# power.net
KiCad netlist of a schematic drawn in Altium Designer
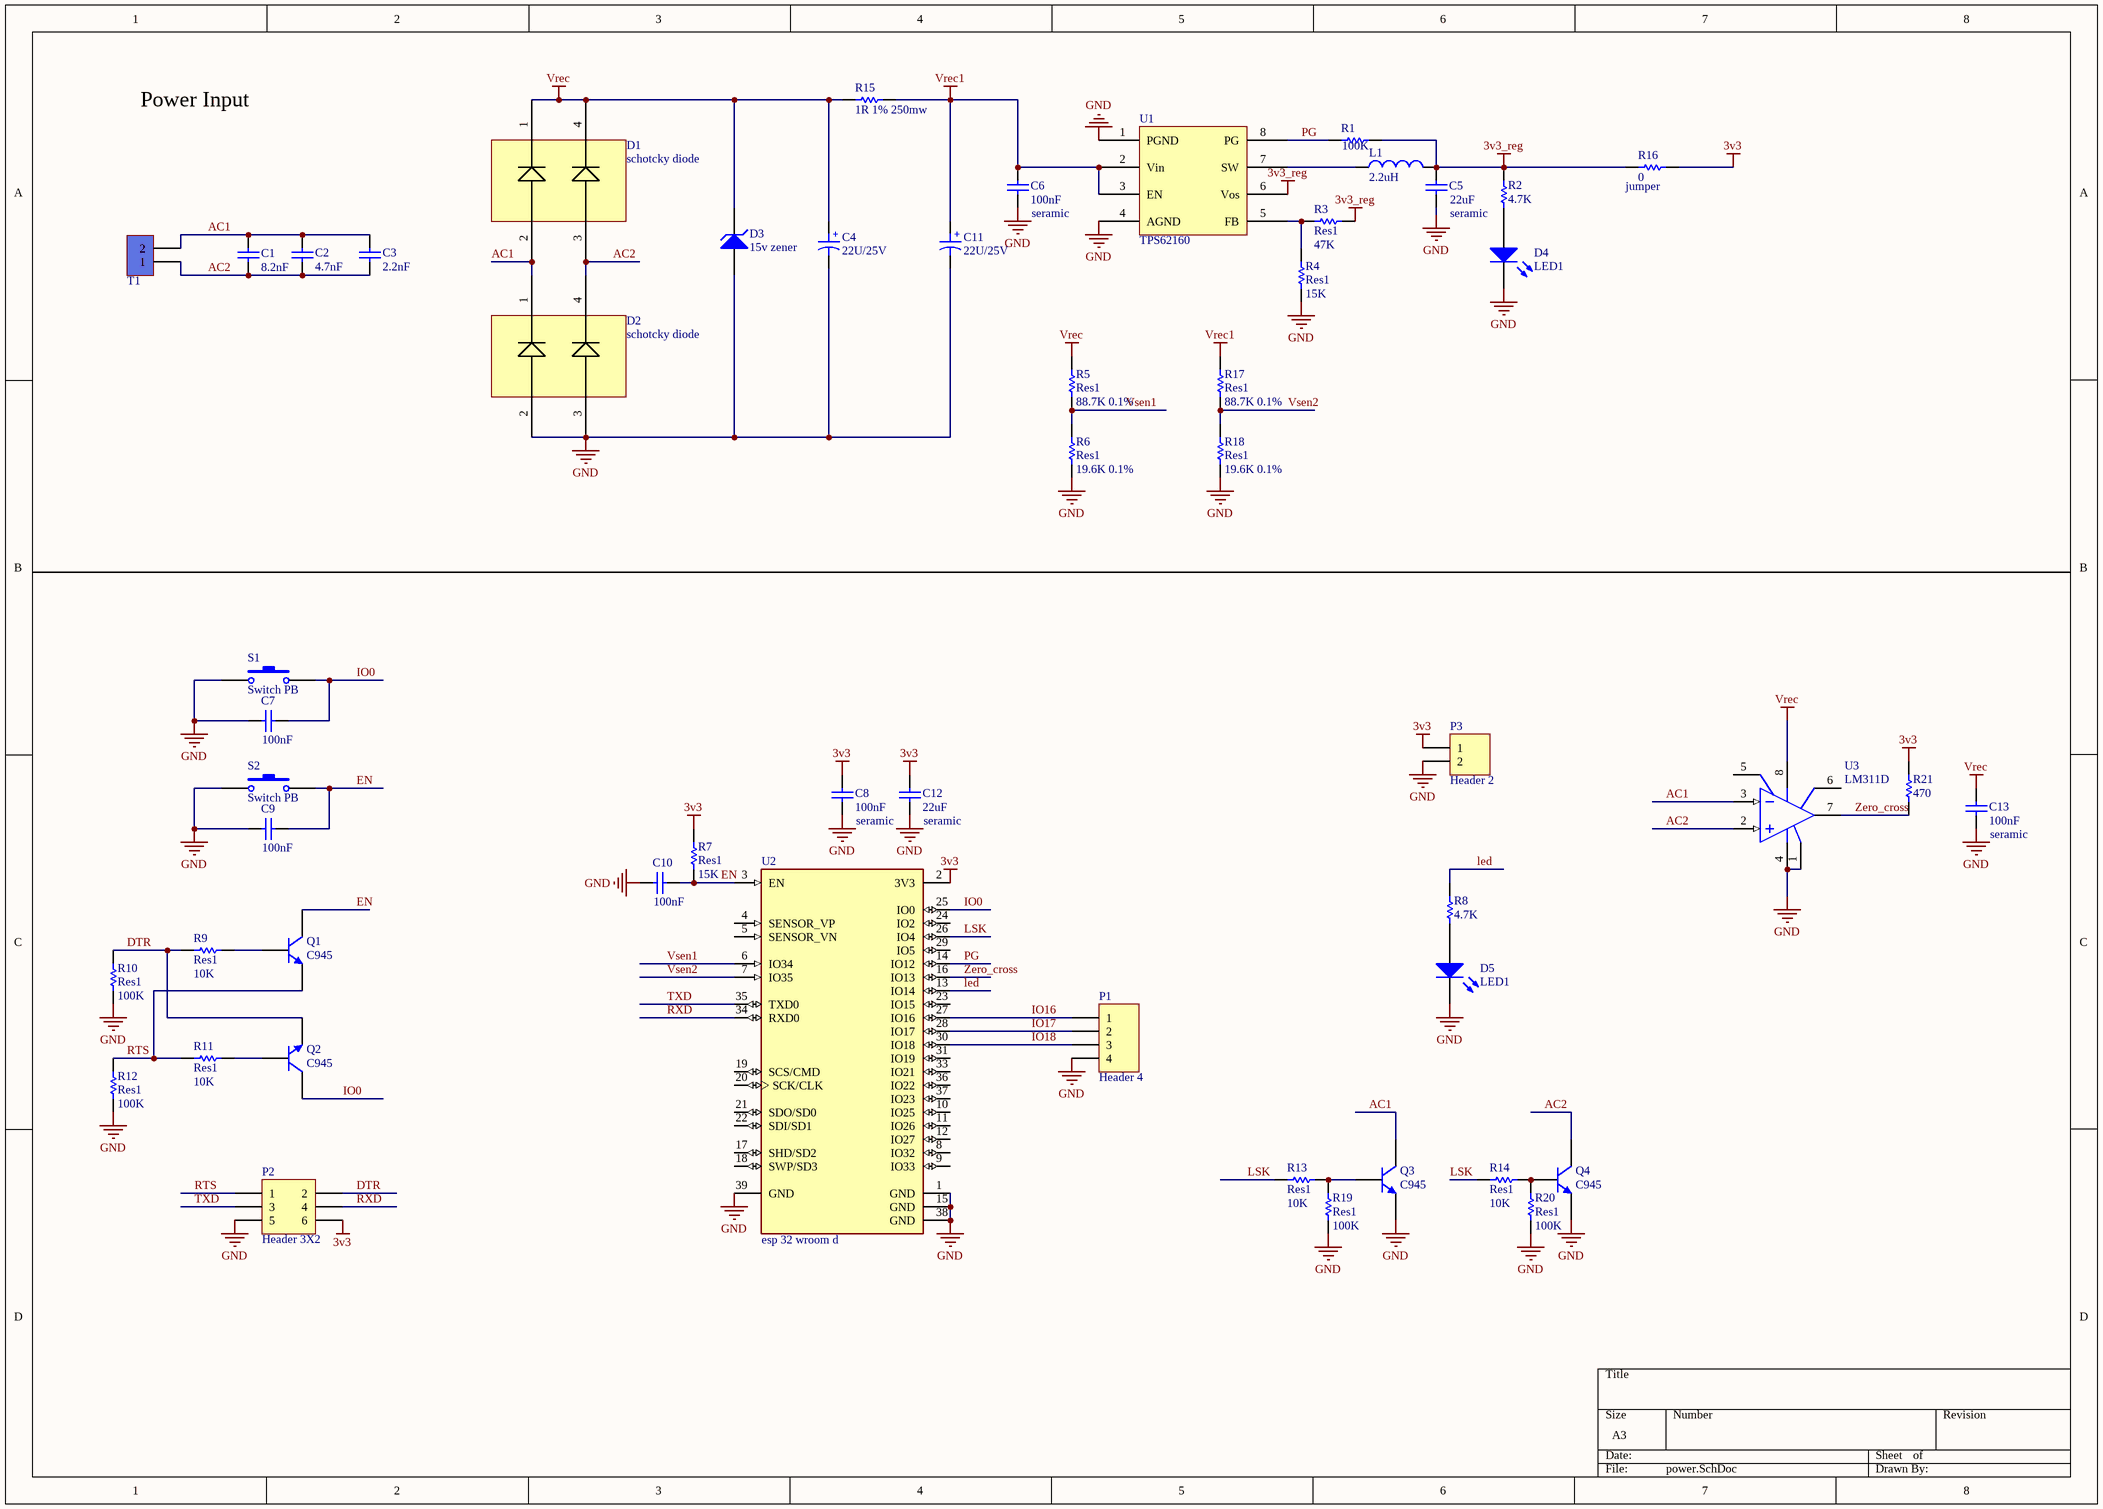
[diagram p0: power.SchDoc]

(export (version "E")
  (design (tool "Eeschema 10.0.6"))
  (components
    (comp (ref "C1")
      (value "8.2nF")
      (footprint "Cap 1206 (3216X15L)")
      (description "Capacitor")
      (fields (field (name "Comment") "Cap") (field (name "PUBLISHER") "Altium Limited"))
      (libsource (lib "Miscellaneous Devices") (part "Cap"))
    )
    (comp (ref "C2")
      (value "4.7nF")
      (footprint "Cap 1206 (3216X15L)")
      (description "Capacitor")
      (fields (field (name "Comment") "Cap") (field (name "PUBLISHER") "Altium Limited"))
      (libsource (lib "Miscellaneous Devices") (part "Cap"))
    )
    (comp (ref "C3")
      (value "2.2nF")
      (footprint "Cap 1206 (3216X15L)")
      (description "Capacitor")
      (fields (field (name "Comment") "Cap") (field (name "PUBLISHER") "Altium Limited"))
      (libsource (lib "Miscellaneous Devices") (part "Cap"))
    )
    (comp (ref "C4")
      (value "Cap tantal")
      (footprint "Cap1206_(3216X18L)Size A")
      (fields (field (name "PART. NO") "22U/25V") (field (name "DESIGNER") "Abbas Basereh"))
      (libsource (lib "Altium (2)") (part "Cap electrolitic radial 10x21"))
    )
    (comp (ref "C5")
      (value "seramic")
      (footprint "SMD_CAP_0805")
      (description "Capacitor")
      (fields (field (name "ALTIUM_VALUE") "22uF") (field (name "PUBLISHER") "Altium Limited"))
      (libsource (lib "Miscellaneous Devices") (part "Cap"))
    )
    (comp (ref "C6")
      (value "seramic")
      (footprint "SMD_CAP_0805")
      (description "Capacitor")
      (fields (field (name "ALTIUM_VALUE") "100nF") (field (name "PUBLISHER") "Altium Limited"))
      (libsource (lib "Miscellaneous Devices") (part "Cap"))
    )
    (comp (ref "C7")
      (value "100nF")
      (footprint "SMD_CAP_0805")
      (description "Capacitor")
      (fields (field (name "Comment") "seramic") (field (name "PUBLISHER") "Altium Limited"))
      (libsource (lib "Miscellaneous Devices") (part "Cap"))
    )
    (comp (ref "C8")
      (value "seramic")
      (footprint "SMD_CAP_0805")
      (description "Capacitor")
      (fields (field (name "ALTIUM_VALUE") "100nF") (field (name "PUBLISHER") "Altium Limited"))
      (libsource (lib "Miscellaneous Devices") (part "Cap"))
    )
    (comp (ref "C9")
      (value "100nF")
      (footprint "SMD_CAP_0805")
      (description "Capacitor")
      (fields (field (name "Comment") "seramic") (field (name "PUBLISHER") "Altium Limited"))
      (libsource (lib "Miscellaneous Devices") (part "Cap"))
    )
    (comp (ref "C10")
      (value "100nF")
      (footprint "SMD_CAP_0805")
      (description "Capacitor")
      (fields (field (name "Comment") "seramic") (field (name "PUBLISHER") "Altium Limited"))
      (libsource (lib "Miscellaneous Devices") (part "Cap"))
    )
    (comp (ref "C11")
      (value "Cap tantal")
      (footprint "Cap1206_(3216X18L)Size A")
      (fields (field (name "PART. NO") "22U/25V") (field (name "DESIGNER") "Abbas Basereh"))
      (libsource (lib "Altium (2)") (part "Cap electrolitic radial 10x21"))
    )
    (comp (ref "C12")
      (value "seramic")
      (footprint "SMD_CAP_0805")
      (description "Capacitor")
      (fields (field (name "ALTIUM_VALUE") "22uF") (field (name "PUBLISHER") "Altium Limited"))
      (libsource (lib "Miscellaneous Devices") (part "Cap"))
    )
    (comp (ref "C13")
      (value "seramic")
      (footprint "SMD_CAP_0805")
      (description "Capacitor")
      (fields (field (name "ALTIUM_VALUE") "100nF") (field (name "PUBLISHER") "Altium Limited"))
      (libsource (lib "Miscellaneous Devices") (part "Cap"))
    )
    (comp (ref "D1")
      (value "schotcky diode")
      (footprint "UMD4")
      (libsource (lib "reciver_sch") (part "RB481"))
    )
    (comp (ref "D2")
      (value "schotcky diode")
      (footprint "UMD4")
      (libsource (lib "reciver_sch") (part "RB481"))
    )
    (comp (ref "D3")
      (value "15v zener")
      (footprint "Diode 1n4148 SMD")
      (description "Zener Diode")
      (fields (field (name "PUBLISHER") "Altium Limited"))
      (libsource (lib "Miscellaneous Devices") (part "D Zener"))
    )
    (comp (ref "D4")
      (value "LED1")
      (footprint "led_0805")
      (description "Typical RED GaAs LED")
      (fields (field (name "PUBLISHER") "Altium Limited"))
      (libsource (lib "Miscellaneous Devices") (part "LED1"))
    )
    (comp (ref "D5")
      (value "LED1")
      (footprint "led_0805")
      (description "Typical RED GaAs LED")
      (fields (field (name "PUBLISHER") "Altium Limited"))
      (libsource (lib "Miscellaneous Devices") (part "LED1"))
    )
    (comp (ref "L1")
      (value "2.2uH")
      (footprint "IND1210")
      (description "Inductor")
      (fields (field (name "PUBLISHER") "Altium Limited"))
      (libsource (lib "Altium (2)") (part "Inductor"))
    )
    (comp (ref "P1")
      (value "Header 4")
      (footprint "header-1.27mm-1*4")
      (description "Header, 4-Pin")
      (fields (field (name "PUBLISHER") "Altium Limited"))
      (libsource (lib "Miscellaneous Connectors") (part "Header 4"))
    )
    (comp (ref "P2")
      (value "Header 3X2")
      (footprint "header-1.27mm-smd-2*3")
      (description "Header, 3-Pin, Dual row")
      (fields (field (name "PUBLISHER") "Altium Limited"))
      (libsource (lib "Miscellaneous Connectors") (part "Header 3X2"))
    )
    (comp (ref "P3")
      (value "Header 2")
      (footprint "HDR1X2")
      (description "Header, 2-Pin")
      (fields (field (name "PUBLISHER") "Altium Limited"))
      (libsource (lib "Miscellaneous Connectors") (part "Header 2"))
    )
    (comp (ref "Q1")
      (value "C945")
      (footprint "SOT23_N")
      (description "NPN Silicon Epitaxial Planar Transistor")
      (fields (field (name "PUBLISHER") "Abbas Basereh"))
      (libsource (lib "Altium (2)") (part "C945"))
    )
    (comp (ref "Q2")
      (value "C945")
      (footprint "SOT23_N")
      (description "NPN Silicon Epitaxial Planar Transistor")
      (fields (field (name "PUBLISHER") "Abbas Basereh"))
      (libsource (lib "Altium (2)") (part "C945"))
    )
    (comp (ref "Q3")
      (value "C945")
      (footprint "SOT23_N")
      (description "NPN Silicon Epitaxial Planar Transistor")
      (fields (field (name "PUBLISHER") "Abbas Basereh"))
      (libsource (lib "Altium (2)") (part "C945"))
    )
    (comp (ref "Q4")
      (value "C945")
      (footprint "SOT23_N")
      (description "NPN Silicon Epitaxial Planar Transistor")
      (fields (field (name "PUBLISHER") "Abbas Basereh"))
      (libsource (lib "Altium (2)") (part "C945"))
    )
    (comp (ref "R1")
      (value "100K")
      (footprint "RES 0805 (2012X06L)")
      (description "Resistor")
      (fields (field (name "Comment") "Res1") (field (name "PUBLISHER") "Altium Limited"))
      (libsource (lib "Miscellaneous Devices") (part "Res1"))
    )
    (comp (ref "R2")
      (value "4.7K")
      (footprint "RES 0805 (2012X06L)")
      (description "Resistor")
      (fields (field (name "Comment") "Res1") (field (name "PUBLISHER") "Altium Limited"))
      (libsource (lib "Miscellaneous Devices") (part "Res1"))
    )
    (comp (ref "R3")
      (value "Res1")
      (footprint "RES 0805 (2012X06L)")
      (description "Resistor")
      (fields (field (name "ALTIUM_VALUE") "47K") (field (name "PUBLISHER") "Altium Limited"))
      (libsource (lib "Miscellaneous Devices") (part "Res1"))
    )
    (comp (ref "R4")
      (value "Res1")
      (footprint "RES 0805 (2012X06L)")
      (description "Resistor")
      (fields (field (name "ALTIUM_VALUE") "15K") (field (name "PUBLISHER") "Altium Limited"))
      (libsource (lib "Miscellaneous Devices") (part "Res1"))
    )
    (comp (ref "R5")
      (value "Res1")
      (footprint "RES 0805 (2012X06L)")
      (description "Resistor")
      (fields (field (name "ALTIUM_VALUE") "88.7K 0.1%") (field (name "PUBLISHER") "Altium Limited"))
      (libsource (lib "Miscellaneous Devices") (part "Res1"))
    )
    (comp (ref "R6")
      (value "Res1")
      (footprint "RES 0805 (2012X06L)")
      (description "Resistor")
      (fields (field (name "ALTIUM_VALUE") "19.6K 0.1%") (field (name "PUBLISHER") "Altium Limited"))
      (libsource (lib "Miscellaneous Devices") (part "Res1"))
    )
    (comp (ref "R7")
      (value "Res1")
      (footprint "RES 0805 (2012X06L)")
      (description "Resistor")
      (fields (field (name "ALTIUM_VALUE") "15K") (field (name "PUBLISHER") "Altium Limited"))
      (libsource (lib "Miscellaneous Devices") (part "Res1"))
    )
    (comp (ref "R8")
      (value "4.7K")
      (footprint "RES 0805 (2012X06L)")
      (description "Resistor")
      (fields (field (name "Comment") "Res1") (field (name "PUBLISHER") "Altium Limited"))
      (libsource (lib "Miscellaneous Devices") (part "Res1"))
    )
    (comp (ref "R9")
      (value "Res1")
      (footprint "RES 0805 (2012X06L)")
      (description "Resistor")
      (fields (field (name "ALTIUM_VALUE") "10K") (field (name "PUBLISHER") "Altium Limited"))
      (libsource (lib "Miscellaneous Devices") (part "Res1"))
    )
    (comp (ref "R10")
      (value "Res1")
      (footprint "RES 0805 (2012X06L)")
      (description "Resistor")
      (fields (field (name "ALTIUM_VALUE") "100K") (field (name "PUBLISHER") "Altium Limited"))
      (libsource (lib "Miscellaneous Devices") (part "Res1"))
    )
    (comp (ref "R11")
      (value "Res1")
      (footprint "RES 0805 (2012X06L)")
      (description "Resistor")
      (fields (field (name "ALTIUM_VALUE") "10K") (field (name "PUBLISHER") "Altium Limited"))
      (libsource (lib "Miscellaneous Devices") (part "Res1"))
    )
    (comp (ref "R12")
      (value "Res1")
      (footprint "RES 0805 (2012X06L)")
      (description "Resistor")
      (fields (field (name "ALTIUM_VALUE") "100K") (field (name "PUBLISHER") "Altium Limited"))
      (libsource (lib "Miscellaneous Devices") (part "Res1"))
    )
    (comp (ref "R13")
      (value "Res1")
      (footprint "RES 0805 (2012X06L)")
      (description "Resistor")
      (fields (field (name "ALTIUM_VALUE") "10K") (field (name "PUBLISHER") "Altium Limited"))
      (libsource (lib "Miscellaneous Devices") (part "Res1"))
    )
    (comp (ref "R14")
      (value "Res1")
      (footprint "RES 0805 (2012X06L)")
      (description "Resistor")
      (fields (field (name "ALTIUM_VALUE") "10K") (field (name "PUBLISHER") "Altium Limited"))
      (libsource (lib "Miscellaneous Devices") (part "Res1"))
    )
    (comp (ref "R15")
      (value "1R 1% 250mw")
      (footprint "RES 1206 (3216X08L)")
      (description "Resistor")
      (fields (field (name "Comment") "Res1") (field (name "PUBLISHER") "Altium Limited"))
      (libsource (lib "Miscellaneous Devices") (part "Res1"))
    )
    (comp (ref "R16")
      (value "jumper")
      (footprint "Jumper")
      (description "Resistor")
      (fields (field (name "ALTIUM_VALUE") "0") (field (name "PUBLISHER") "Altium Limited"))
      (libsource (lib "Miscellaneous Devices") (part "Res1"))
    )
    (comp (ref "R17")
      (value "Res1")
      (footprint "RES 0805 (2012X06L)")
      (description "Resistor")
      (fields (field (name "ALTIUM_VALUE") "88.7K 0.1%") (field (name "PUBLISHER") "Altium Limited"))
      (libsource (lib "Miscellaneous Devices") (part "Res1"))
    )
    (comp (ref "R18")
      (value "Res1")
      (footprint "RES 0805 (2012X06L)")
      (description "Resistor")
      (fields (field (name "ALTIUM_VALUE") "19.6K 0.1%") (field (name "PUBLISHER") "Altium Limited"))
      (libsource (lib "Miscellaneous Devices") (part "Res1"))
    )
    (comp (ref "R19")
      (value "Res1")
      (footprint "RES 0805 (2012X06L)")
      (description "Resistor")
      (fields (field (name "ALTIUM_VALUE") "100K") (field (name "PUBLISHER") "Altium Limited"))
      (libsource (lib "Miscellaneous Devices") (part "Res1"))
    )
    (comp (ref "R20")
      (value "Res1")
      (footprint "RES 0805 (2012X06L)")
      (description "Resistor")
      (fields (field (name "ALTIUM_VALUE") "100K") (field (name "PUBLISHER") "Altium Limited"))
      (libsource (lib "Miscellaneous Devices") (part "Res1"))
    )
    (comp (ref "R21")
      (value "470")
      (footprint "RES 0805 (2012X06L)")
      (description "Resistor")
      (fields (field (name "Comment") "Res1") (field (name "PUBLISHER") "Altium Limited"))
      (libsource (lib "Miscellaneous Devices") (part "Res1"))
    )
    (comp (ref "S1")
      (value "Switch PB")
      (footprint "tack-sw-3x5x6")
      (description "Push Button Switch")
      (libsource (lib "My Library") (part "Switch PB"))
    )
    (comp (ref "S2")
      (value "Switch PB")
      (footprint "tack-sw-3x5x6")
      (description "Push Button Switch")
      (libsource (lib "My Library") (part "Switch PB"))
    )
    (comp (ref "T1")
      (value "Terminal")
      (footprint "my-term")
      (description "Terminal 2 Pin 250VAC 16A")
      (fields (field (name "DESIGNER") "Seyed Mohsen Ghasemain") (field (name "E-MAIL") "picpars@gmail.com"))
      (libsource (lib "PicPars.com_usefully_Library") (part "Terminal 1*2"))
    )
    (comp (ref "U1")
      (value "TPS62160")
      (footprint "DGK-PDSO-G8")
      (libsource (lib "reciver_sch") (part "TPS62160"))
    )
    (comp (ref "U2")
      (value "esp 32 wroom d")
      (footprint "esp-wroom")
      (libsource (lib "reciver_sch") (part "ESP32-wroom"))
    )
    (comp (ref "U3")
      (value "LM311D")
      (footprint "SO8_N")
      (description "Voltage Comparator")
      (fields (field (name "PUBLISHER") "Altium Limited"))
      (libsource (lib "ST Analog Comparator") (part "LM311D"))
    )
  )
  (nets
    (net (code "1") (name "/AC1") (class "Default")
      (node (ref "C1") (pin "2") (pinfunction "2_2") (pintype "passive"))
      (node (ref "C2") (pin "2") (pinfunction "2_2") (pintype "passive"))
      (node (ref "C3") (pin "2") (pinfunction "2_2") (pintype "passive"))
      (node (ref "D1") (pin "2") (pinfunction "A1_2") (pintype "passive"))
      (node (ref "D2") (pin "1") (pinfunction "K1_1") (pintype "passive"))
      (node (ref "Q3") (pin "3") (pinfunction "C_3") (pintype "passive"))
      (node (ref "T1") (pin "2") (pinfunction "2_2") (pintype "passive"))
      (node (ref "U3") (pin "3") (pinfunction "IN-_3") (pintype "input"))
    )
    (net (code "2") (name "/AC2") (class "Default")
      (node (ref "C1") (pin "1") (pinfunction "1_1") (pintype "passive"))
      (node (ref "C2") (pin "1") (pinfunction "1_1") (pintype "passive"))
      (node (ref "C3") (pin "1") (pinfunction "1_1") (pintype "passive"))
      (node (ref "D1") (pin "3") (pinfunction "A2_3") (pintype "passive"))
      (node (ref "D2") (pin "4") (pinfunction "K2_4") (pintype "passive"))
      (node (ref "Q4") (pin "3") (pinfunction "C_3") (pintype "passive"))
      (node (ref "T1") (pin "1") (pinfunction "1_1") (pintype "passive"))
      (node (ref "U3") (pin "2") (pinfunction "IN+_2") (pintype "input"))
    )
    (net (code "3") (name "/DTR") (class "Default")
      (node (ref "P2") (pin "2") (pinfunction "2_2") (pintype "passive"))
      (node (ref "Q2") (pin "2") (pinfunction "E_2") (pintype "passive"))
      (node (ref "R10") (pin "1") (pinfunction "1_1") (pintype "passive"))
      (node (ref "R9") (pin "1") (pinfunction "1_1") (pintype "passive"))
    )
    (net (code "4") (name "/EN") (class "Default")
      (node (ref "C10") (pin "1") (pinfunction "1_1") (pintype "passive"))
      (node (ref "C9") (pin "1") (pinfunction "1_1") (pintype "passive"))
      (node (ref "Q1") (pin "3") (pinfunction "C_3") (pintype "passive"))
      (node (ref "R7") (pin "2") (pinfunction "2_2") (pintype "passive"))
      (node (ref "S2") (pin "2") (pinfunction "2_2") (pintype "passive"))
      (node (ref "U2") (pin "3") (pinfunction "EN_3") (pintype "input"))
    )
    (net (code "5") (name "/IO0") (class "Default")
      (node (ref "C7") (pin "1") (pinfunction "1_1") (pintype "passive"))
      (node (ref "Q2") (pin "3") (pinfunction "C_3") (pintype "passive"))
      (node (ref "S1") (pin "2") (pinfunction "2_2") (pintype "passive"))
      (node (ref "U2") (pin "25") (pinfunction "IO0_25") (pintype "bidirectional"))
    )
    (net (code "6") (name "/IO16") (class "Default")
      (node (ref "P1") (pin "1") (pinfunction "1_1") (pintype "passive"))
      (node (ref "U2") (pin "27") (pinfunction "IO16_27") (pintype "bidirectional"))
    )
    (net (code "7") (name "/IO17") (class "Default")
      (node (ref "P1") (pin "2") (pinfunction "2_2") (pintype "passive"))
      (node (ref "U2") (pin "28") (pinfunction "IO17_28") (pintype "bidirectional"))
    )
    (net (code "8") (name "/IO18") (class "Default")
      (node (ref "P1") (pin "3") (pinfunction "3_3") (pintype "passive"))
      (node (ref "U2") (pin "30") (pinfunction "IO18_30") (pintype "bidirectional"))
    )
    (net (code "9") (name "/LSK") (class "Default")
      (node (ref "R13") (pin "1") (pinfunction "1_1") (pintype "passive"))
      (node (ref "R14") (pin "1") (pinfunction "1_1") (pintype "passive"))
      (node (ref "U2") (pin "26") (pinfunction "IO4_26") (pintype "bidirectional"))
    )
    (net (code "10") (name "/PG") (class "Default")
      (node (ref "R1") (pin "2") (pinfunction "2_2") (pintype "passive"))
      (node (ref "U1") (pin "8") (pinfunction "PG_8") (pintype "passive"))
      (node (ref "U2") (pin "14") (pinfunction "IO12_14") (pintype "bidirectional"))
    )
    (net (code "11") (name "/RTS") (class "Default")
      (node (ref "P2") (pin "1") (pinfunction "1_1") (pintype "passive"))
      (node (ref "Q1") (pin "2") (pinfunction "E_2") (pintype "passive"))
      (node (ref "R11") (pin "1") (pinfunction "1_1") (pintype "passive"))
      (node (ref "R12") (pin "1") (pinfunction "1_1") (pintype "passive"))
    )
    (net (code "12") (name "/RXD") (class "Default")
      (node (ref "P2") (pin "4") (pinfunction "4_4") (pintype "passive"))
      (node (ref "U2") (pin "34") (pinfunction "RXD0_34") (pintype "bidirectional"))
    )
    (net (code "13") (name "/TXD") (class "Default")
      (node (ref "P2") (pin "3") (pinfunction "3_3") (pintype "passive"))
      (node (ref "U2") (pin "35") (pinfunction "TXD0_35") (pintype "bidirectional"))
    )
    (net (code "14") (name "/Vsen1") (class "Default")
      (node (ref "R5") (pin "2") (pinfunction "2_2") (pintype "passive"))
      (node (ref "R6") (pin "1") (pinfunction "1_1") (pintype "passive"))
      (node (ref "U2") (pin "6") (pinfunction "IO34_6") (pintype "input"))
    )
    (net (code "15") (name "/Vsen2") (class "Default")
      (node (ref "R17") (pin "2") (pinfunction "2_2") (pintype "passive"))
      (node (ref "R18") (pin "1") (pinfunction "1_1") (pintype "passive"))
      (node (ref "U2") (pin "7") (pinfunction "IO35_7") (pintype "input"))
    )
    (net (code "16") (name "/Zero_cross") (class "Default")
      (node (ref "R21") (pin "2") (pinfunction "2_2") (pintype "passive"))
      (node (ref "U2") (pin "16") (pinfunction "IO13_16") (pintype "bidirectional"))
      (node (ref "U3") (pin "7") (pinfunction "OUT_7") (pintype "open_collector"))
    )
    (net (code "17") (name "/led") (class "Default")
      (node (ref "R8") (pin "1") (pinfunction "1_1") (pintype "passive"))
      (node (ref "U2") (pin "13") (pinfunction "IO14_13") (pintype "bidirectional"))
    )
    (net (code "18") (name "3v3") (class "Default")
      (node (ref "C12") (pin "2") (pinfunction "2_2") (pintype "passive"))
      (node (ref "C8") (pin "2") (pinfunction "2_2") (pintype "passive"))
      (node (ref "P2") (pin "6") (pinfunction "6_6") (pintype "passive"))
      (node (ref "P3") (pin "1") (pinfunction "1_1") (pintype "passive"))
      (node (ref "R16") (pin "2") (pinfunction "2_2") (pintype "passive"))
      (node (ref "R21") (pin "1") (pinfunction "1_1") (pintype "passive"))
      (node (ref "R7") (pin "1") (pinfunction "1_1") (pintype "passive"))
      (node (ref "U2") (pin "2") (pinfunction "3V3_2") (pintype "power_in"))
    )
    (net (code "19") (name "3v3_reg") (class "Default")
      (node (ref "C5") (pin "2") (pinfunction "2_2") (pintype "passive"))
      (node (ref "L1") (pin "2") (pinfunction "2_2") (pintype "passive"))
      (node (ref "R1") (pin "1") (pinfunction "1_1") (pintype "passive"))
      (node (ref "R16") (pin "1") (pinfunction "1_1") (pintype "passive"))
      (node (ref "R2") (pin "1") (pinfunction "1_1") (pintype "passive"))
      (node (ref "R3") (pin "1") (pinfunction "1_1") (pintype "passive"))
      (node (ref "U1") (pin "6") (pinfunction "Vos_6") (pintype "passive"))
    )
    (net (code "20") (name "GND") (class "Default")
      (node (ref "C10") (pin "2") (pinfunction "2_2") (pintype "passive"))
      (node (ref "C11") (pin "2") (pinfunction "2_2") (pintype "passive"))
      (node (ref "C12") (pin "1") (pinfunction "1_1") (pintype "passive"))
      (node (ref "C13") (pin "1") (pinfunction "1_1") (pintype "passive"))
      (node (ref "C4") (pin "2") (pinfunction "2_2") (pintype "passive"))
      (node (ref "C5") (pin "1") (pinfunction "1_1") (pintype "passive"))
      (node (ref "C6") (pin "1") (pinfunction "1_1") (pintype "passive"))
      (node (ref "C7") (pin "2") (pinfunction "2_2") (pintype "passive"))
      (node (ref "C8") (pin "1") (pinfunction "1_1") (pintype "passive"))
      (node (ref "C9") (pin "2") (pinfunction "2_2") (pintype "passive"))
      (node (ref "D2") (pin "2") (pinfunction "A1_2") (pintype "passive"))
      (node (ref "D2") (pin "3") (pinfunction "A2_3") (pintype "passive"))
      (node (ref "D3") (pin "1") (pinfunction "A_1") (pintype "passive"))
      (node (ref "D4") (pin "2") (pinfunction "K_2") (pintype "passive"))
      (node (ref "D5") (pin "2") (pinfunction "K_2") (pintype "passive"))
      (node (ref "P1") (pin "4") (pinfunction "4_4") (pintype "passive"))
      (node (ref "P2") (pin "5") (pinfunction "5_5") (pintype "passive"))
      (node (ref "P3") (pin "2") (pinfunction "2_2") (pintype "passive"))
      (node (ref "Q3") (pin "2") (pinfunction "E_2") (pintype "passive"))
      (node (ref "Q4") (pin "2") (pinfunction "E_2") (pintype "passive"))
      (node (ref "R10") (pin "2") (pinfunction "2_2") (pintype "passive"))
      (node (ref "R12") (pin "2") (pinfunction "2_2") (pintype "passive"))
      (node (ref "R18") (pin "2") (pinfunction "2_2") (pintype "passive"))
      (node (ref "R19") (pin "1") (pinfunction "1_1") (pintype "passive"))
      (node (ref "R20") (pin "1") (pinfunction "1_1") (pintype "passive"))
      (node (ref "R4") (pin "2") (pinfunction "2_2") (pintype "passive"))
      (node (ref "R6") (pin "2") (pinfunction "2_2") (pintype "passive"))
      (node (ref "S1") (pin "1") (pinfunction "1_1") (pintype "passive"))
      (node (ref "S2") (pin "1") (pinfunction "1_1") (pintype "passive"))
      (node (ref "U1") (pin "1") (pinfunction "PGND_1") (pintype "passive"))
      (node (ref "U1") (pin "4") (pinfunction "AGND_4") (pintype "passive"))
      (node (ref "U2") (pin "1") (pinfunction "GND_1") (pintype "power_in"))
      (node (ref "U2") (pin "15") (pinfunction "GND_15") (pintype "power_in"))
      (node (ref "U2") (pin "38") (pinfunction "GND_38") (pintype "power_in"))
      (node (ref "U2") (pin "39") (pinfunction "GND_39") (pintype "power_in"))
      (node (ref "U3") (pin "1") (pinfunction "GND_1") (pintype "power_in"))
      (node (ref "U3") (pin "4") (pinfunction "V-_(CASE)_4") (pintype "power_in"))
    )
    (net (code "21") (name "Net-(D4-A)") (class "Default")
      (node (ref "D4") (pin "1") (pinfunction "A_1") (pintype "passive"))
      (node (ref "R2") (pin "2") (pinfunction "2_2") (pintype "passive"))
    )
    (net (code "22") (name "Net-(D5-A)") (class "Default")
      (node (ref "D5") (pin "1") (pinfunction "A_1") (pintype "passive"))
      (node (ref "R8") (pin "2") (pinfunction "2_2") (pintype "passive"))
    )
    (net (code "23") (name "Net-(Q1-B)") (class "Default")
      (node (ref "Q1") (pin "1") (pinfunction "B_1") (pintype "passive"))
      (node (ref "R9") (pin "2") (pinfunction "2_2") (pintype "passive"))
    )
    (net (code "24") (name "Net-(Q2-B)") (class "Default")
      (node (ref "Q2") (pin "1") (pinfunction "B_1") (pintype "passive"))
      (node (ref "R11") (pin "2") (pinfunction "2_2") (pintype "passive"))
    )
    (net (code "25") (name "Net-(Q3-B)") (class "Default")
      (node (ref "Q3") (pin "1") (pinfunction "B_1") (pintype "passive"))
      (node (ref "R13") (pin "2") (pinfunction "2_2") (pintype "passive"))
      (node (ref "R19") (pin "2") (pinfunction "2_2") (pintype "passive"))
    )
    (net (code "26") (name "Net-(Q4-B)") (class "Default")
      (node (ref "Q4") (pin "1") (pinfunction "B_1") (pintype "passive"))
      (node (ref "R14") (pin "2") (pinfunction "2_2") (pintype "passive"))
      (node (ref "R20") (pin "2") (pinfunction "2_2") (pintype "passive"))
    )
    (net (code "27") (name "Net-(U1-FB)") (class "Default")
      (node (ref "R3") (pin "2") (pinfunction "2_2") (pintype "passive"))
      (node (ref "R4") (pin "1") (pinfunction "1_1") (pintype "passive"))
      (node (ref "U1") (pin "5") (pinfunction "FB_5") (pintype "passive"))
    )
    (net (code "28") (name "Net-(U1-SW)") (class "Default")
      (node (ref "L1") (pin "1") (pinfunction "1_1") (pintype "passive"))
      (node (ref "U1") (pin "7") (pinfunction "SW_7") (pintype "passive"))
    )
    (net (code "29") (name "Vrec") (class "Default")
      (node (ref "C13") (pin "2") (pinfunction "2_2") (pintype "passive"))
      (node (ref "C4") (pin "1") (pinfunction "1_1") (pintype "passive"))
      (node (ref "D1") (pin "1") (pinfunction "K1_1") (pintype "passive"))
      (node (ref "D1") (pin "4") (pinfunction "K2_4") (pintype "passive"))
      (node (ref "D3") (pin "2") (pinfunction "K_2") (pintype "passive"))
      (node (ref "R15") (pin "1") (pinfunction "1_1") (pintype "passive"))
      (node (ref "R5") (pin "1") (pinfunction "1_1") (pintype "passive"))
      (node (ref "U3") (pin "8") (pinfunction "V+_8") (pintype "power_in"))
    )
    (net (code "30") (name "Vrec1") (class "Default")
      (node (ref "C11") (pin "1") (pinfunction "1_1") (pintype "passive"))
      (node (ref "C6") (pin "2") (pinfunction "2_2") (pintype "passive"))
      (node (ref "R15") (pin "2") (pinfunction "2_2") (pintype "passive"))
      (node (ref "R17") (pin "1") (pinfunction "1_1") (pintype "passive"))
      (node (ref "U1") (pin "2") (pinfunction "Vin_2") (pintype "passive"))
      (node (ref "U1") (pin "3") (pinfunction "EN_3") (pintype "passive"))
    )
    (net (code "31") (name "unconnected-(U2-IO2-Pad24)") (class "Default")
      (node (ref "U2") (pin "24") (pinfunction "IO2_24") (pintype "bidirectional"))
    )
    (net (code "32") (name "unconnected-(U2-IO5-Pad29)") (class "Default")
      (node (ref "U2") (pin "29") (pinfunction "IO5_29") (pintype "bidirectional"))
    )
    (net (code "33") (name "unconnected-(U2-IO15-Pad23)") (class "Default")
      (node (ref "U2") (pin "23") (pinfunction "IO15_23") (pintype "bidirectional"))
    )
    (net (code "34") (name "unconnected-(U2-IO19-Pad31)") (class "Default")
      (node (ref "U2") (pin "31") (pinfunction "IO19_31") (pintype "bidirectional"))
    )
    (net (code "35") (name "unconnected-(U2-IO21-Pad33)") (class "Default")
      (node (ref "U2") (pin "33") (pinfunction "IO21_33") (pintype "bidirectional"))
    )
    (net (code "36") (name "unconnected-(U2-IO22-Pad36)") (class "Default")
      (node (ref "U2") (pin "36") (pinfunction "IO22_36") (pintype "bidirectional"))
    )
    (net (code "37") (name "unconnected-(U2-IO23-Pad37)") (class "Default")
      (node (ref "U2") (pin "37") (pinfunction "IO23_37") (pintype "bidirectional"))
    )
    (net (code "38") (name "unconnected-(U2-IO25-Pad10)") (class "Default")
      (node (ref "U2") (pin "10") (pinfunction "IO25_10") (pintype "bidirectional"))
    )
    (net (code "39") (name "unconnected-(U2-IO26-Pad11)") (class "Default")
      (node (ref "U2") (pin "11") (pinfunction "IO26_11") (pintype "bidirectional"))
    )
    (net (code "40") (name "unconnected-(U2-IO27-Pad12)") (class "Default")
      (node (ref "U2") (pin "12") (pinfunction "IO27_12") (pintype "bidirectional"))
    )
    (net (code "41") (name "unconnected-(U2-IO32-Pad8)") (class "Default")
      (node (ref "U2") (pin "8") (pinfunction "IO32_8") (pintype "bidirectional"))
    )
    (net (code "42") (name "unconnected-(U2-IO33-Pad9)") (class "Default")
      (node (ref "U2") (pin "9") (pinfunction "IO33_9") (pintype "bidirectional"))
    )
    (net (code "43") (name "unconnected-(U2-SCK{slash}CLK-Pad20)") (class "Default")
      (node (ref "U2") (pin "20") (pinfunction "SCK/CLK_20") (pintype "bidirectional"))
    )
    (net (code "44") (name "unconnected-(U2-SCS{slash}CMD-Pad19)") (class "Default")
      (node (ref "U2") (pin "19") (pinfunction "SCS/CMD_19") (pintype "bidirectional"))
    )
    (net (code "45") (name "unconnected-(U2-SDI{slash}SD1-Pad22)") (class "Default")
      (node (ref "U2") (pin "22") (pinfunction "SDI/SD1_22") (pintype "bidirectional"))
    )
    (net (code "46") (name "unconnected-(U2-SDO{slash}SD0-Pad21)") (class "Default")
      (node (ref "U2") (pin "21") (pinfunction "SDO/SD0_21") (pintype "bidirectional"))
    )
    (net (code "47") (name "unconnected-(U2-SENSOR_VN-Pad5)") (class "Default")
      (node (ref "U2") (pin "5") (pinfunction "SENSOR_VN_5") (pintype "input"))
    )
    (net (code "48") (name "unconnected-(U2-SENSOR_VP-Pad4)") (class "Default")
      (node (ref "U2") (pin "4") (pinfunction "SENSOR_VP_4") (pintype "input"))
    )
    (net (code "49") (name "unconnected-(U2-SHD{slash}SD2-Pad17)") (class "Default")
      (node (ref "U2") (pin "17") (pinfunction "SHD/SD2_17") (pintype "bidirectional"))
    )
    (net (code "50") (name "unconnected-(U2-SWP{slash}SD3-Pad18)") (class "Default")
      (node (ref "U2") (pin "18") (pinfunction "SWP/SD3_18") (pintype "bidirectional"))
    )
    (net (code "51") (name "unconnected-(U3-BAL-Pad5)") (class "Default")
      (node (ref "U3") (pin "5") (pinfunction "BAL_5") (pintype "passive"))
    )
    (net (code "52") (name "unconnected-(U3-BAL{slash}STB-Pad6)") (class "Default")
      (node (ref "U3") (pin "6") (pinfunction "BAL/STB_6") (pintype "passive"))
    )
  )
)
